# GPIO.net
KiCad netlist of a schematic drawn in Altium Designer
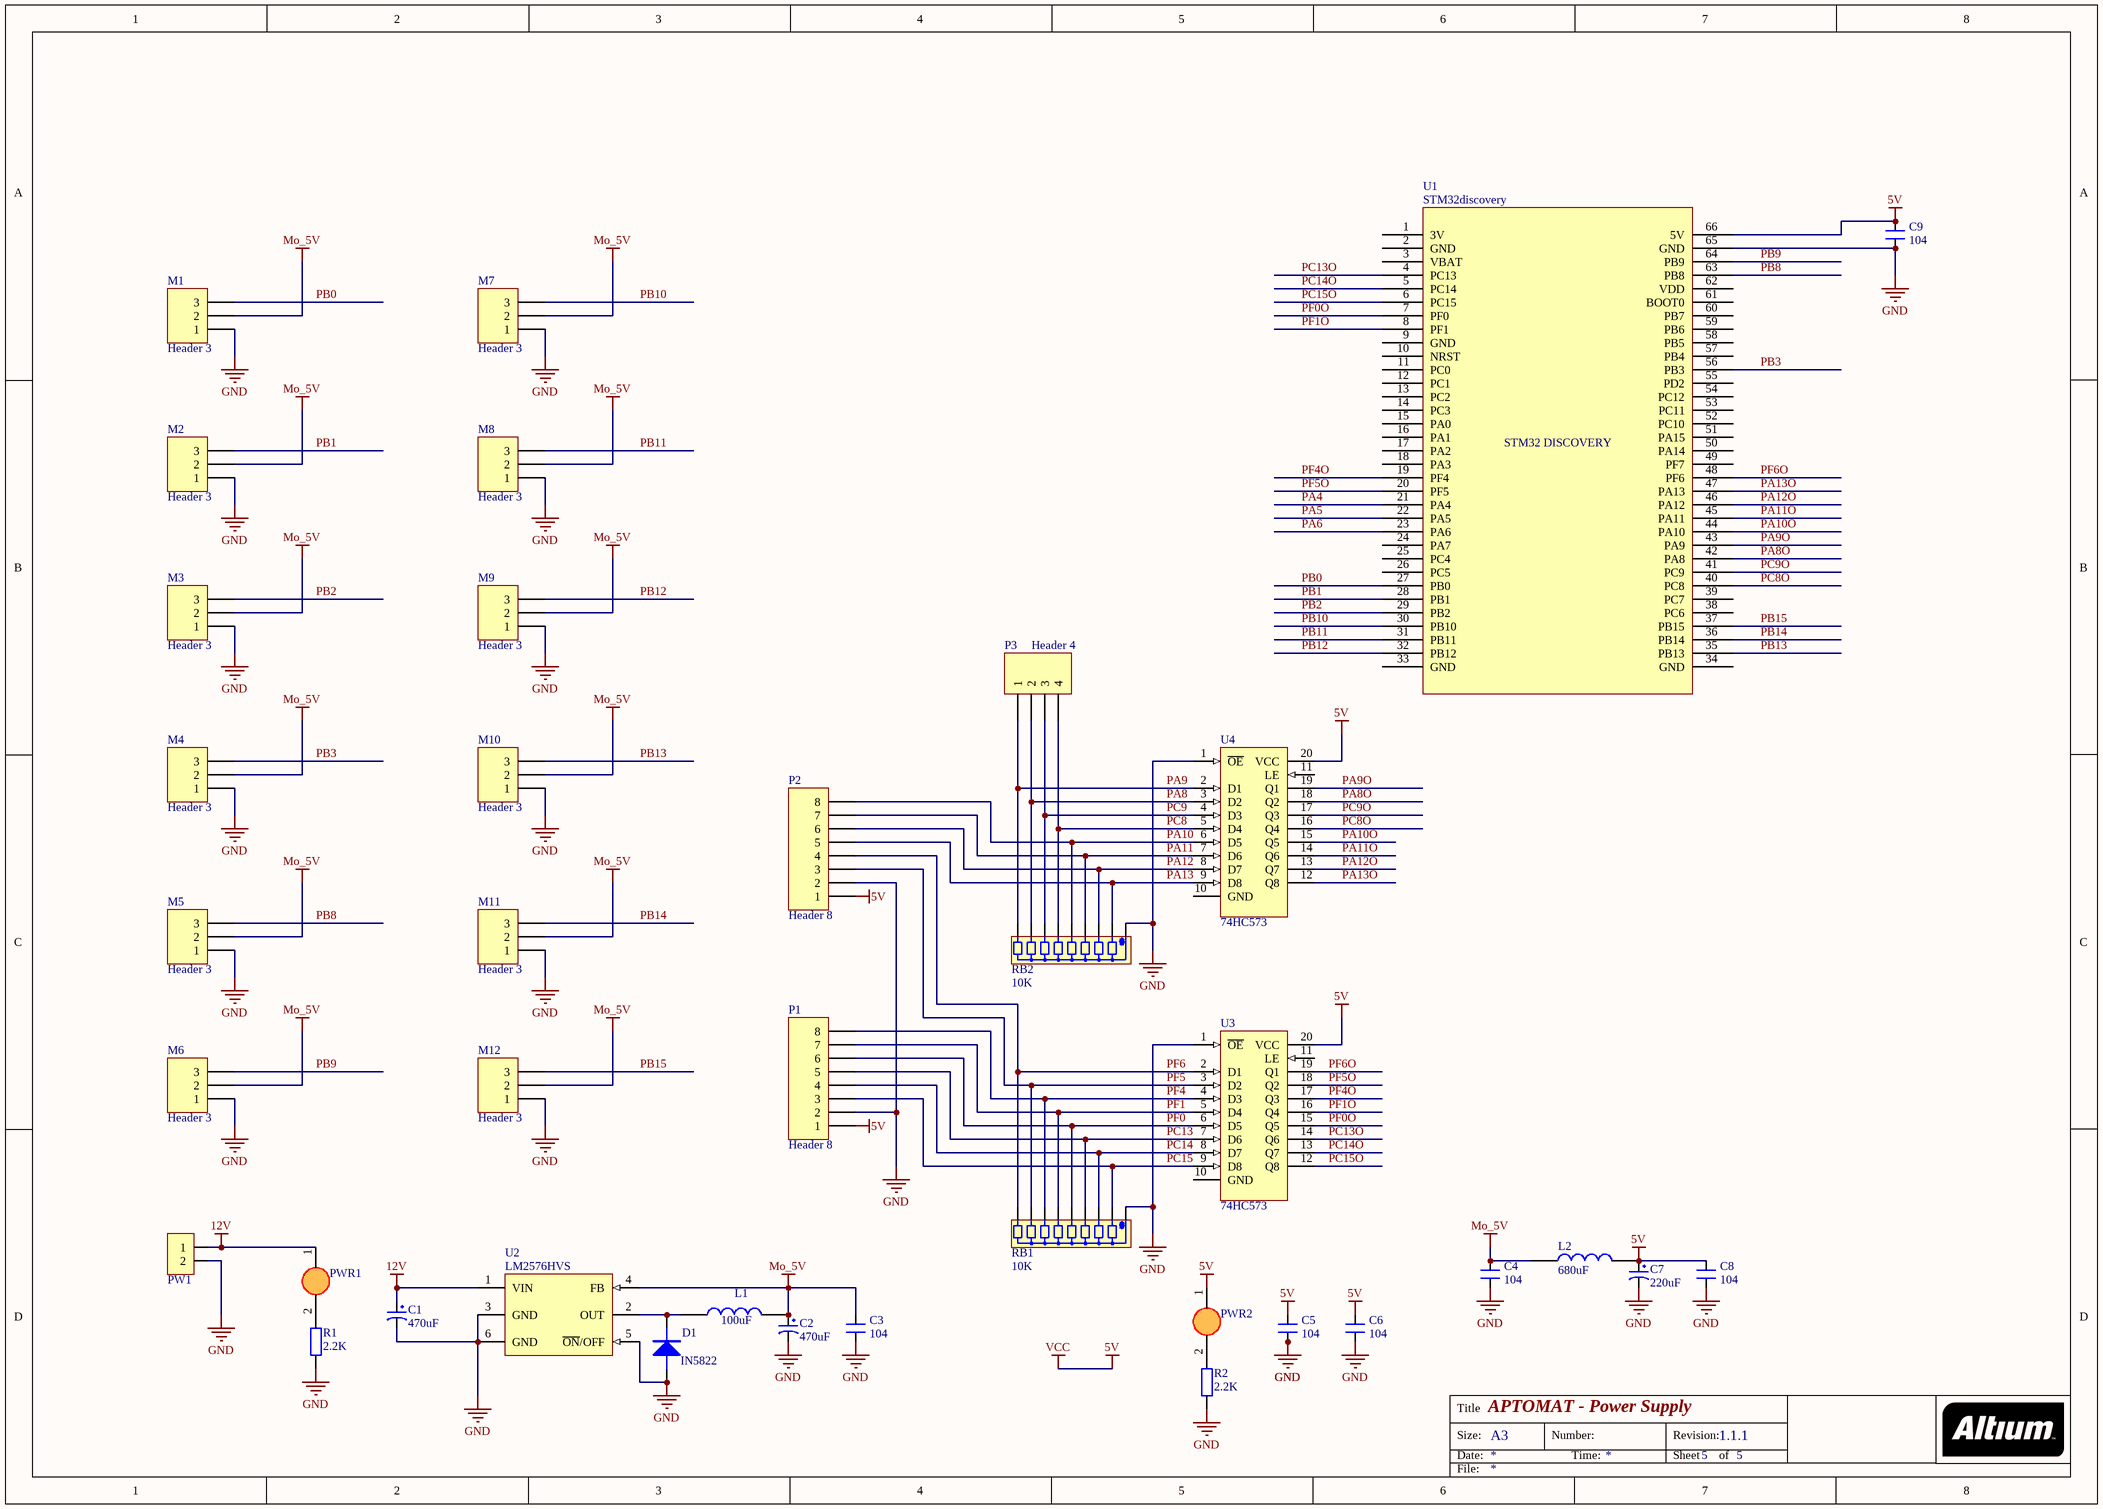
[diagram p0: GPIO.SchDoc]

(export (version "E")
  (design (tool "Eeschema 10.0.6"))
  (components
    (comp (ref "C1")
      (value "470uF")
      (footprint "TU_NHOM_470uF_25V_MH")
      (description "TU_NHOM_470uF_25V_MH")
      (libsource (lib "MH_DA_THU_VIEN_16122016") (part "TU_NHOM_470uF_25V_MH"))
    )
    (comp (ref "C2")
      (value "470uF")
      (footprint "TU_NHOM_470uF_25V_MH")
      (description "TU_NHOM_470uF_25V_MH")
      (libsource (lib "MH_DA_THU_VIEN_16122016") (part "TU_NHOM_470uF_25V_MH"))
    )
    (comp (ref "C3")
      (value "104")
      (footprint "0805_HV")
      (description "Cap SMD")
      (libsource (lib "hatcatbietbay") (part "CM"))
    )
    (comp (ref "C4")
      (value "104")
      (footprint "0805_HV")
      (description "Cap SMD")
      (libsource (lib "hatcatbietbay") (part "CM"))
    )
    (comp (ref "C5")
      (value "104")
      (footprint "0805_HV")
      (description "Cap SMD")
      (libsource (lib "hatcatbietbay") (part "CM"))
    )
    (comp (ref "C6")
      (value "104")
      (footprint "0805_HV")
      (description "Cap SMD")
      (libsource (lib "hatcatbietbay") (part "CM"))
    )
    (comp (ref "C7")
      (value "220uF")
      (footprint "TU_NHOM_2.5_MH")
      (description "TU_NHOM_220uF_25V_MH")
      (libsource (lib "MH_DA_THU_VIEN_16122016") (part "TU_NHOM_220uF_25V_MH"))
    )
    (comp (ref "C8")
      (value "104")
      (footprint "0805_HV")
      (description "Cap SMD")
      (libsource (lib "hatcatbietbay") (part "CM"))
    )
    (comp (ref "C9")
      (value "104")
      (footprint "0805_HV")
      (description "Cap SMD")
      (libsource (lib "hatcatbietbay") (part "CM"))
    )
    (comp (ref "D1")
      (value "IN5822")
      (footprint "SOD123")
      (description "Diode S4 SOD123 ( 1N5819 SOD123)")
      (libsource (lib "MH_DA_THU_VIEN_16122016") (part "Diode S4 SOD123 ( 1N5819 SOD123)_MH"))
    )
    (comp (ref "L1")
      (value "100uF")
      (footprint "IND_2118-V-RC")
      (description "cuon cam")
      (libsource (lib "MH_DA_THU_VIEN_16122016") (part "Inductor Lm2576_MH"))
    )
    (comp (ref "L2")
      (value "680uF")
      (footprint "Inductor 4.5x5")
      (libsource (lib "MH_DA_THU_VIEN_16122016") (part "Inductor 4.5x5_MH"))
    )
    (comp (ref "M1")
      (value "Header 3")
      (footprint "HDR1X3")
      (description "Header, 3-Pin")
      (fields (field (name "PUBLISHER") "Altium Limited"))
      (libsource (lib "Miscellaneous Connectors") (part "Header 3"))
    )
    (comp (ref "M2")
      (value "Header 3")
      (footprint "HDR1X3")
      (description "Header, 3-Pin")
      (fields (field (name "PUBLISHER") "Altium Limited"))
      (libsource (lib "Miscellaneous Connectors") (part "Header 3"))
    )
    (comp (ref "M3")
      (value "Header 3")
      (footprint "HDR1X3")
      (description "Header, 3-Pin")
      (fields (field (name "PUBLISHER") "Altium Limited"))
      (libsource (lib "Miscellaneous Connectors") (part "Header 3"))
    )
    (comp (ref "M4")
      (value "Header 3")
      (footprint "HDR1X3")
      (description "Header, 3-Pin")
      (fields (field (name "PUBLISHER") "Altium Limited"))
      (libsource (lib "Miscellaneous Connectors") (part "Header 3"))
    )
    (comp (ref "M5")
      (value "Header 3")
      (footprint "HDR1X3")
      (description "Header, 3-Pin")
      (fields (field (name "PUBLISHER") "Altium Limited"))
      (libsource (lib "Miscellaneous Connectors") (part "Header 3"))
    )
    (comp (ref "M6")
      (value "Header 3")
      (footprint "HDR1X3")
      (description "Header, 3-Pin")
      (fields (field (name "PUBLISHER") "Altium Limited"))
      (libsource (lib "Miscellaneous Connectors") (part "Header 3"))
    )
    (comp (ref "M7")
      (value "Header 3")
      (footprint "HDR1X3")
      (description "Header, 3-Pin")
      (fields (field (name "PUBLISHER") "Altium Limited"))
      (libsource (lib "Miscellaneous Connectors") (part "Header 3"))
    )
    (comp (ref "M8")
      (value "Header 3")
      (footprint "HDR1X3")
      (description "Header, 3-Pin")
      (fields (field (name "PUBLISHER") "Altium Limited"))
      (libsource (lib "Miscellaneous Connectors") (part "Header 3"))
    )
    (comp (ref "M9")
      (value "Header 3")
      (footprint "HDR1X3")
      (description "Header, 3-Pin")
      (fields (field (name "PUBLISHER") "Altium Limited"))
      (libsource (lib "Miscellaneous Connectors") (part "Header 3"))
    )
    (comp (ref "M10")
      (value "Header 3")
      (footprint "HDR1X3")
      (description "Header, 3-Pin")
      (fields (field (name "PUBLISHER") "Altium Limited"))
      (libsource (lib "Miscellaneous Connectors") (part "Header 3"))
    )
    (comp (ref "M11")
      (value "Header 3")
      (footprint "HDR1X3")
      (description "Header, 3-Pin")
      (fields (field (name "PUBLISHER") "Altium Limited"))
      (libsource (lib "Miscellaneous Connectors") (part "Header 3"))
    )
    (comp (ref "M12")
      (value "Header 3")
      (footprint "HDR1X3")
      (description "Header, 3-Pin")
      (fields (field (name "PUBLISHER") "Altium Limited"))
      (libsource (lib "Miscellaneous Connectors") (part "Header 3"))
    )
    (comp (ref "P1")
      (value "Header 8")
      (footprint "HEADER2M_8P")
      (description "Header, 8-Pin")
      (fields (field (name "PUBLISHER") "Altium Limited"))
      (libsource (lib "Miscellaneous Connectors") (part "Header 8"))
    )
    (comp (ref "P2")
      (value "Header 8")
      (footprint "HEADER2M_8P")
      (description "Header, 8-Pin")
      (fields (field (name "PUBLISHER") "Altium Limited"))
      (libsource (lib "Miscellaneous Connectors") (part "Header 8"))
    )
    (comp (ref "P3")
      (value "Header 4")
      (footprint "HDR1X4")
      (description "Header, 4-Pin")
      (fields (field (name "PUBLISHER") "Altium Limited"))
      (libsource (lib "Miscellaneous Connectors") (part "Header 4"))
    )
    (comp (ref "PW1")
      (value "CON 2 EDG 5.08_MH")
      (footprint "CON 2 EDG 5.08")
      (description "CON 2 EDG 5.08 (xanh cong)")
      (libsource (lib "MH_DA_THU_VIEN_16122016") (part "CON 2 EDG 5.08_MH"))
    )
    (comp (ref "PWR1")
      (value "LED3")
      (footprint "LED_0805")
      (description "LED 3mm")
      (libsource (lib "MH_DA_THU_VIEN_16122016") (part "LED SMD_0805_MH"))
    )
    (comp (ref "PWR2")
      (value "LED3")
      (footprint "LED_0805")
      (description "LED 3mm")
      (libsource (lib "MH_DA_THU_VIEN_16122016") (part "LED SMD_0805_MH"))
    )
    (comp (ref "R1")
      (value "2.2K")
      (footprint "MH_DA_THU_VIEN_16122016:Tro SMD 0805")
      (description "TRO_SMD_0805_MH")
      (libsource (lib "MH_DA_THU_VIEN_16122016") (part "TRO_SMD_0805_MH"))
    )
    (comp (ref "R2")
      (value "2.2K")
      (footprint "MH_DA_THU_VIEN_16122016:Tro SMD 0805")
      (description "TRO_SMD_0805_MH")
      (libsource (lib "MH_DA_THU_VIEN_16122016") (part "TRO_SMD_0805_MH"))
    )
    (comp (ref "RB1")
      (value "TRO_BANG_A09_MH")
      (footprint "TRO_BANG_A09")
      (fields (field (name "ALTIUM_UNNAMED_1") "10K"))
      (libsource (lib "MH_DA_THU_VIEN_16122016") (part "TRO_BANG_A09_MH"))
    )
    (comp (ref "RB2")
      (value "TRO_BANG_A09_MH")
      (footprint "TRO_BANG_A09")
      (fields (field (name "ALTIUM_UNNAMED_1") "10K"))
      (libsource (lib "MH_DA_THU_VIEN_16122016") (part "TRO_BANG_A09_MH"))
    )
    (comp (ref "U1")
      (value "STM32discovery")
      (footprint "STM32discovery_kit")
      (libsource (lib "Schlib1") (part "STM32Discovery_kit"))
    )
    (comp (ref "U2")
      (value "LM2576HVS")
      (footprint "TO263-5")
      (description "LM2576HVS-5.0V BUCK 5V 3A TO263-5 _MH")
      (fields
        (field (name "PARTNUMBER") "LM2576T-5.0")
        (field (name "MANUFACTURER") "National Semiconductor")
        (field (name "PUBLISHER") "Altium Limited")
      )
      (libsource (lib "MH_DA_THU_VIEN_16122016") (part "LM2576HVS-5.0V BUCK 5V 3A TO263-5 _MH"))
    )
    (comp (ref "U3")
      (value "74HC573")
      (footprint "DIP20")
      (description "Octal D-Type Latch with 3-State Output Non-Inverting")
      (fields (field (name "COPYRIGHT BY") "VanDungEvn@Gmail.com"))
      (libsource (lib "MH_DA_THU_VIEN_16122016") (part "74HC573 DIP20 IC Flip-Flop_MH"))
    )
    (comp (ref "U4")
      (value "74HC573")
      (footprint "DIP20")
      (description "Octal D-Type Latch with 3-State Output Non-Inverting")
      (fields (field (name "COPYRIGHT BY") "VanDungEvn@Gmail.com"))
      (libsource (lib "MH_DA_THU_VIEN_16122016") (part "74HC573 DIP20 IC Flip-Flop_MH"))
    )
  )
  (nets
    (net (code "1") (name "/PA4") (class "Default")
      (node (ref "U1") (pin "21") (pinfunction "PA4_21") (pintype "passive"))
    )
    (net (code "2") (name "/PA5") (class "Default")
      (node (ref "U1") (pin "22") (pinfunction "PA5_22") (pintype "passive"))
    )
    (net (code "3") (name "/PA6") (class "Default")
      (node (ref "U1") (pin "23") (pinfunction "PA6_23") (pintype "passive"))
    )
    (net (code "4") (name "/PA8") (class "Default")
      (node (ref "P3") (pin "2") (pinfunction "2_2") (pintype "passive"))
      (node (ref "RB2") (pin "8") (pinfunction "8_8") (pintype "passive"))
      (node (ref "U4") (pin "3") (pinfunction "D2_3") (pintype "input"))
    )
    (net (code "5") (name "/PA8O") (class "Default")
      (node (ref "U1") (pin "42") (pinfunction "PA8_42") (pintype "passive"))
      (node (ref "U4") (pin "18") (pinfunction "Q2_18") (pintype "tri_state"))
    )
    (net (code "6") (name "/PA9") (class "Default")
      (node (ref "P3") (pin "1") (pinfunction "1_1") (pintype "passive"))
      (node (ref "RB2") (pin "9") (pinfunction "9_9") (pintype "passive"))
      (node (ref "U4") (pin "2") (pinfunction "D1_2") (pintype "input"))
    )
    (net (code "7") (name "/PA9O") (class "Default")
      (node (ref "U1") (pin "43") (pinfunction "PA9_43") (pintype "passive"))
      (node (ref "U4") (pin "19") (pinfunction "Q1_19") (pintype "tri_state"))
    )
    (net (code "8") (name "/PA10") (class "Default")
      (node (ref "P2") (pin "8") (pinfunction "8_8") (pintype "passive"))
      (node (ref "RB2") (pin "5") (pinfunction "5_5") (pintype "passive"))
      (node (ref "U4") (pin "6") (pinfunction "D5_6") (pintype "input"))
    )
    (net (code "9") (name "/PA10O") (class "Default")
      (node (ref "U1") (pin "44") (pinfunction "PA10_44") (pintype "passive"))
      (node (ref "U4") (pin "15") (pinfunction "Q5_15") (pintype "tri_state"))
    )
    (net (code "10") (name "/PA11") (class "Default")
      (node (ref "P2") (pin "7") (pinfunction "7_7") (pintype "passive"))
      (node (ref "RB2") (pin "4") (pinfunction "4_4") (pintype "passive"))
      (node (ref "U4") (pin "7") (pinfunction "D6_7") (pintype "input"))
    )
    (net (code "11") (name "/PA11O") (class "Default")
      (node (ref "U1") (pin "45") (pinfunction "PA11_45") (pintype "passive"))
      (node (ref "U4") (pin "14") (pinfunction "Q6_14") (pintype "tri_state"))
    )
    (net (code "12") (name "/PA12") (class "Default")
      (node (ref "P2") (pin "6") (pinfunction "6_6") (pintype "passive"))
      (node (ref "RB2") (pin "3") (pinfunction "3_3") (pintype "passive"))
      (node (ref "U4") (pin "8") (pinfunction "D7_8") (pintype "input"))
    )
    (net (code "13") (name "/PA12O") (class "Default")
      (node (ref "U1") (pin "46") (pinfunction "PA12_46") (pintype "passive"))
      (node (ref "U4") (pin "13") (pinfunction "Q7_13") (pintype "tri_state"))
    )
    (net (code "14") (name "/PA13") (class "Default")
      (node (ref "P2") (pin "5") (pinfunction "5_5") (pintype "passive"))
      (node (ref "RB2") (pin "2") (pinfunction "2_2") (pintype "passive"))
      (node (ref "U4") (pin "9") (pinfunction "D8_9") (pintype "input"))
    )
    (net (code "15") (name "/PA13O") (class "Default")
      (node (ref "U1") (pin "47") (pinfunction "PA13_47") (pintype "passive"))
      (node (ref "U4") (pin "12") (pinfunction "Q8_12") (pintype "tri_state"))
    )
    (net (code "16") (name "/PB0") (class "Default")
      (node (ref "M1") (pin "3") (pinfunction "3_3") (pintype "passive"))
      (node (ref "U1") (pin "27") (pinfunction "PB0_27") (pintype "passive"))
    )
    (net (code "17") (name "/PB1") (class "Default")
      (node (ref "M2") (pin "3") (pinfunction "3_3") (pintype "passive"))
      (node (ref "U1") (pin "28") (pinfunction "PB1_28") (pintype "passive"))
    )
    (net (code "18") (name "/PB2") (class "Default")
      (node (ref "M3") (pin "3") (pinfunction "3_3") (pintype "passive"))
      (node (ref "U1") (pin "29") (pinfunction "PB2_29") (pintype "passive"))
    )
    (net (code "19") (name "/PB3") (class "Default")
      (node (ref "M4") (pin "3") (pinfunction "3_3") (pintype "passive"))
      (node (ref "U1") (pin "56") (pinfunction "PB3_56") (pintype "passive"))
    )
    (net (code "20") (name "/PB8") (class "Default")
      (node (ref "M5") (pin "3") (pinfunction "3_3") (pintype "passive"))
      (node (ref "U1") (pin "63") (pinfunction "PB8_63") (pintype "passive"))
    )
    (net (code "21") (name "/PB9") (class "Default")
      (node (ref "M6") (pin "3") (pinfunction "3_3") (pintype "passive"))
      (node (ref "U1") (pin "64") (pinfunction "PB9_64") (pintype "passive"))
    )
    (net (code "22") (name "/PB10") (class "Default")
      (node (ref "M7") (pin "3") (pinfunction "3_3") (pintype "passive"))
      (node (ref "U1") (pin "30") (pinfunction "PB10_30") (pintype "passive"))
    )
    (net (code "23") (name "/PB11") (class "Default")
      (node (ref "M8") (pin "3") (pinfunction "3_3") (pintype "passive"))
      (node (ref "U1") (pin "31") (pinfunction "PB11_31") (pintype "passive"))
    )
    (net (code "24") (name "/PB12") (class "Default")
      (node (ref "M9") (pin "3") (pinfunction "3_3") (pintype "passive"))
      (node (ref "U1") (pin "32") (pinfunction "PB12_32") (pintype "passive"))
    )
    (net (code "25") (name "/PB13") (class "Default")
      (node (ref "M10") (pin "3") (pinfunction "3_3") (pintype "passive"))
      (node (ref "U1") (pin "35") (pinfunction "PB13_35") (pintype "passive"))
    )
    (net (code "26") (name "/PB14") (class "Default")
      (node (ref "M11") (pin "3") (pinfunction "3_3") (pintype "passive"))
      (node (ref "U1") (pin "36") (pinfunction "PB14_36") (pintype "passive"))
    )
    (net (code "27") (name "/PB15") (class "Default")
      (node (ref "M12") (pin "3") (pinfunction "3_3") (pintype "passive"))
      (node (ref "U1") (pin "37") (pinfunction "PB15_37") (pintype "passive"))
    )
    (net (code "28") (name "/PC8") (class "Default")
      (node (ref "P3") (pin "4") (pinfunction "4_4") (pintype "passive"))
      (node (ref "RB2") (pin "6") (pinfunction "6_6") (pintype "passive"))
      (node (ref "U4") (pin "5") (pinfunction "D4_5") (pintype "input"))
    )
    (net (code "29") (name "/PC8O") (class "Default")
      (node (ref "U1") (pin "40") (pinfunction "PC8_40") (pintype "passive"))
      (node (ref "U4") (pin "16") (pinfunction "Q4_16") (pintype "tri_state"))
    )
    (net (code "30") (name "/PC9") (class "Default")
      (node (ref "P3") (pin "3") (pinfunction "3_3") (pintype "passive"))
      (node (ref "RB2") (pin "7") (pinfunction "7_7") (pintype "passive"))
      (node (ref "U4") (pin "4") (pinfunction "D3_4") (pintype "input"))
    )
    (net (code "31") (name "/PC9O") (class "Default")
      (node (ref "U1") (pin "41") (pinfunction "PC9_41") (pintype "passive"))
      (node (ref "U4") (pin "17") (pinfunction "Q3_17") (pintype "tri_state"))
    )
    (net (code "32") (name "/PC13") (class "Default")
      (node (ref "P1") (pin "5") (pinfunction "5_5") (pintype "passive"))
      (node (ref "RB1") (pin "4") (pinfunction "4_4") (pintype "passive"))
      (node (ref "U3") (pin "7") (pinfunction "D6_7") (pintype "input"))
    )
    (net (code "33") (name "/PC13O") (class "Default")
      (node (ref "U1") (pin "4") (pinfunction "PC13_4") (pintype "passive"))
      (node (ref "U3") (pin "14") (pinfunction "Q6_14") (pintype "tri_state"))
    )
    (net (code "34") (name "/PC14") (class "Default")
      (node (ref "P1") (pin "4") (pinfunction "4_4") (pintype "passive"))
      (node (ref "RB1") (pin "3") (pinfunction "3_3") (pintype "passive"))
      (node (ref "U3") (pin "8") (pinfunction "D7_8") (pintype "input"))
    )
    (net (code "35") (name "/PC14O") (class "Default")
      (node (ref "U1") (pin "5") (pinfunction "PC14_5") (pintype "passive"))
      (node (ref "U3") (pin "13") (pinfunction "Q7_13") (pintype "tri_state"))
    )
    (net (code "36") (name "/PC15") (class "Default")
      (node (ref "P1") (pin "3") (pinfunction "3_3") (pintype "passive"))
      (node (ref "RB1") (pin "2") (pinfunction "2_2") (pintype "passive"))
      (node (ref "U3") (pin "9") (pinfunction "D8_9") (pintype "input"))
    )
    (net (code "37") (name "/PC15O") (class "Default")
      (node (ref "U1") (pin "6") (pinfunction "PC15_6") (pintype "passive"))
      (node (ref "U3") (pin "12") (pinfunction "Q8_12") (pintype "tri_state"))
    )
    (net (code "38") (name "/PF0") (class "Default")
      (node (ref "P1") (pin "6") (pinfunction "6_6") (pintype "passive"))
      (node (ref "RB1") (pin "5") (pinfunction "5_5") (pintype "passive"))
      (node (ref "U3") (pin "6") (pinfunction "D5_6") (pintype "input"))
    )
    (net (code "39") (name "/PF0O") (class "Default")
      (node (ref "U1") (pin "7") (pinfunction "PF0_7") (pintype "passive"))
      (node (ref "U3") (pin "15") (pinfunction "Q5_15") (pintype "tri_state"))
    )
    (net (code "40") (name "/PF1") (class "Default")
      (node (ref "P1") (pin "7") (pinfunction "7_7") (pintype "passive"))
      (node (ref "RB1") (pin "6") (pinfunction "6_6") (pintype "passive"))
      (node (ref "U3") (pin "5") (pinfunction "D4_5") (pintype "input"))
    )
    (net (code "41") (name "/PF1O") (class "Default")
      (node (ref "U1") (pin "8") (pinfunction "PF1_8") (pintype "passive"))
      (node (ref "U3") (pin "16") (pinfunction "Q4_16") (pintype "tri_state"))
    )
    (net (code "42") (name "/PF4") (class "Default")
      (node (ref "P1") (pin "8") (pinfunction "8_8") (pintype "passive"))
      (node (ref "RB1") (pin "7") (pinfunction "7_7") (pintype "passive"))
      (node (ref "U3") (pin "4") (pinfunction "D3_4") (pintype "input"))
    )
    (net (code "43") (name "/PF4O") (class "Default")
      (node (ref "U1") (pin "19") (pinfunction "PF4_19") (pintype "passive"))
      (node (ref "U3") (pin "17") (pinfunction "Q3_17") (pintype "tri_state"))
    )
    (net (code "44") (name "/PF5") (class "Default")
      (node (ref "P2") (pin "3") (pinfunction "3_3") (pintype "passive"))
      (node (ref "RB1") (pin "8") (pinfunction "8_8") (pintype "passive"))
      (node (ref "U3") (pin "3") (pinfunction "D2_3") (pintype "input"))
    )
    (net (code "45") (name "/PF5O") (class "Default")
      (node (ref "U1") (pin "20") (pinfunction "PF5_20") (pintype "passive"))
      (node (ref "U3") (pin "18") (pinfunction "Q2_18") (pintype "tri_state"))
    )
    (net (code "46") (name "/PF6") (class "Default")
      (node (ref "P2") (pin "4") (pinfunction "4_4") (pintype "passive"))
      (node (ref "RB1") (pin "9") (pinfunction "9_9") (pintype "passive"))
      (node (ref "U3") (pin "2") (pinfunction "D1_2") (pintype "input"))
    )
    (net (code "47") (name "/PF6O") (class "Default")
      (node (ref "U1") (pin "48") (pinfunction "PF6_48") (pintype "passive"))
      (node (ref "U3") (pin "19") (pinfunction "Q1_19") (pintype "tri_state"))
    )
    (net (code "48") (name "5V") (class "Default")
      (node (ref "C5") (pin "2") (pinfunction "2_2") (pintype "passive"))
      (node (ref "C6") (pin "2") (pinfunction "2_2") (pintype "passive"))
      (node (ref "C7") (pin "1") (pinfunction "1_1") (pintype "passive"))
      (node (ref "C8") (pin "2") (pinfunction "2_2") (pintype "passive"))
      (node (ref "C9") (pin "2") (pinfunction "2_2") (pintype "passive"))
      (node (ref "L2") (pin "2") (pinfunction "2_2") (pintype "passive"))
      (node (ref "P1") (pin "1") (pinfunction "1_1") (pintype "passive"))
      (node (ref "P2") (pin "1") (pinfunction "1_1") (pintype "passive"))
      (node (ref "PWR2") (pin "1") (pinfunction "A_1") (pintype "passive"))
      (node (ref "U1") (pin "66") (pinfunction "5V_66") (pintype "passive"))
      (node (ref "U3") (pin "20") (pinfunction "VCC_20") (pintype "tri_state"))
      (node (ref "U4") (pin "20") (pinfunction "VCC_20") (pintype "tri_state"))
    )
    (net (code "49") (name "12V") (class "Default")
      (node (ref "C1") (pin "1") (pinfunction "1_1") (pintype "passive"))
      (node (ref "PW1") (pin "1") (pinfunction "1_1") (pintype "passive"))
      (node (ref "PWR1") (pin "1") (pinfunction "A_1") (pintype "passive"))
      (node (ref "U2") (pin "1") (pinfunction "VIN_1") (pintype "power_in"))
    )
    (net (code "50") (name "GND") (class "Default")
      (node (ref "C1") (pin "2") (pinfunction "2_2") (pintype "passive"))
      (node (ref "C2") (pin "2") (pinfunction "2_2") (pintype "passive"))
      (node (ref "C3") (pin "1") (pinfunction "1_1") (pintype "passive"))
      (node (ref "C4") (pin "1") (pinfunction "1_1") (pintype "passive"))
      (node (ref "C5") (pin "1") (pinfunction "1_1") (pintype "passive"))
      (node (ref "C6") (pin "1") (pinfunction "1_1") (pintype "passive"))
      (node (ref "C7") (pin "2") (pinfunction "2_2") (pintype "passive"))
      (node (ref "C8") (pin "1") (pinfunction "1_1") (pintype "passive"))
      (node (ref "C9") (pin "1") (pinfunction "1_1") (pintype "passive"))
      (node (ref "D1") (pin "1") (pinfunction "1_1") (pintype "passive"))
      (node (ref "M1") (pin "1") (pinfunction "1_1") (pintype "passive"))
      (node (ref "M10") (pin "1") (pinfunction "1_1") (pintype "passive"))
      (node (ref "M11") (pin "1") (pinfunction "1_1") (pintype "passive"))
      (node (ref "M12") (pin "1") (pinfunction "1_1") (pintype "passive"))
      (node (ref "M2") (pin "1") (pinfunction "1_1") (pintype "passive"))
      (node (ref "M3") (pin "1") (pinfunction "1_1") (pintype "passive"))
      (node (ref "M4") (pin "1") (pinfunction "1_1") (pintype "passive"))
      (node (ref "M5") (pin "1") (pinfunction "1_1") (pintype "passive"))
      (node (ref "M6") (pin "1") (pinfunction "1_1") (pintype "passive"))
      (node (ref "M7") (pin "1") (pinfunction "1_1") (pintype "passive"))
      (node (ref "M8") (pin "1") (pinfunction "1_1") (pintype "passive"))
      (node (ref "M9") (pin "1") (pinfunction "1_1") (pintype "passive"))
      (node (ref "P1") (pin "2") (pinfunction "2_2") (pintype "passive"))
      (node (ref "P2") (pin "2") (pinfunction "2_2") (pintype "passive"))
      (node (ref "PW1") (pin "2") (pinfunction "2_2") (pintype "passive"))
      (node (ref "R1") (pin "1") (pinfunction "1_1") (pintype "passive"))
      (node (ref "R2") (pin "1") (pinfunction "1_1") (pintype "passive"))
      (node (ref "RB1") (pin "1") (pinfunction "1_1") (pintype "passive"))
      (node (ref "RB2") (pin "1") (pinfunction "1_1") (pintype "passive"))
      (node (ref "U1") (pin "65") (pinfunction "GND_65") (pintype "passive"))
      (node (ref "U2") (pin "3") (pinfunction "GND_3") (pintype "power_in"))
      (node (ref "U2") (pin "5") (pinfunction "~{ON}/OFF_5") (pintype "input"))
      (node (ref "U2") (pin "6") (pinfunction "GND_6") (pintype "passive"))
      (node (ref "U3") (pin "1") (pinfunction "~{OE}_1") (pintype "input"))
      (node (ref "U4") (pin "1") (pinfunction "~{OE}_1") (pintype "input"))
    )
    (net (code "51") (name "Mo_5V") (class "Default")
      (node (ref "C2") (pin "1") (pinfunction "1_1") (pintype "passive"))
      (node (ref "C3") (pin "2") (pinfunction "2_2") (pintype "passive"))
      (node (ref "C4") (pin "2") (pinfunction "2_2") (pintype "passive"))
      (node (ref "L1") (pin "2") (pinfunction "2_2") (pintype "passive"))
      (node (ref "L2") (pin "1") (pinfunction "1_1") (pintype "passive"))
      (node (ref "M1") (pin "2") (pinfunction "2_2") (pintype "passive"))
      (node (ref "M10") (pin "2") (pinfunction "2_2") (pintype "passive"))
      (node (ref "M11") (pin "2") (pinfunction "2_2") (pintype "passive"))
      (node (ref "M12") (pin "2") (pinfunction "2_2") (pintype "passive"))
      (node (ref "M2") (pin "2") (pinfunction "2_2") (pintype "passive"))
      (node (ref "M3") (pin "2") (pinfunction "2_2") (pintype "passive"))
      (node (ref "M4") (pin "2") (pinfunction "2_2") (pintype "passive"))
      (node (ref "M5") (pin "2") (pinfunction "2_2") (pintype "passive"))
      (node (ref "M6") (pin "2") (pinfunction "2_2") (pintype "passive"))
      (node (ref "M7") (pin "2") (pinfunction "2_2") (pintype "passive"))
      (node (ref "M8") (pin "2") (pinfunction "2_2") (pintype "passive"))
      (node (ref "M9") (pin "2") (pinfunction "2_2") (pintype "passive"))
      (node (ref "U2") (pin "4") (pinfunction "FB_4") (pintype "input"))
    )
    (net (code "52") (name "Net-(PWR1-K)") (class "Default")
      (node (ref "PWR1") (pin "2") (pinfunction "K_2") (pintype "passive"))
      (node (ref "R1") (pin "2") (pinfunction "2_2") (pintype "passive"))
    )
    (net (code "53") (name "Net-(PWR2-K)") (class "Default")
      (node (ref "PWR2") (pin "2") (pinfunction "K_2") (pintype "passive"))
      (node (ref "R2") (pin "2") (pinfunction "2_2") (pintype "passive"))
    )
    (net (code "54") (name "Net-(U2-OUT)") (class "Default")
      (node (ref "D1") (pin "2") (pinfunction "2_2") (pintype "passive"))
      (node (ref "L1") (pin "1") (pinfunction "1_1") (pintype "passive"))
      (node (ref "U2") (pin "2") (pinfunction "OUT_2") (pintype "power_in"))
    )
    (net (code "55") (name "unconnected-(U1-3V-Pad1)") (class "Default")
      (node (ref "U1") (pin "1") (pinfunction "3V_1") (pintype "passive"))
    )
    (net (code "56") (name "unconnected-(U1-BOOT0-Pad61)") (class "Default")
      (node (ref "U1") (pin "61") (pinfunction "BOOT0_61") (pintype "passive"))
    )
    (net (code "57") (name "unconnected-(U1-GND-Pad2)") (class "Default")
      (node (ref "U1") (pin "2") (pinfunction "GND_2") (pintype "passive"))
    )
    (net (code "58") (name "unconnected-(U1-GND-Pad9)") (class "Default")
      (node (ref "U1") (pin "9") (pinfunction "GND_9") (pintype "passive"))
    )
    (net (code "59") (name "unconnected-(U1-GND-Pad33)") (class "Default")
      (node (ref "U1") (pin "33") (pinfunction "GND_33") (pintype "passive"))
    )
    (net (code "60") (name "unconnected-(U1-GND-Pad34)") (class "Default")
      (node (ref "U1") (pin "34") (pinfunction "GND_34") (pintype "passive"))
    )
    (net (code "61") (name "unconnected-(U1-NRST-Pad10)") (class "Default")
      (node (ref "U1") (pin "10") (pinfunction "NRST_10") (pintype "passive"))
    )
    (net (code "62") (name "unconnected-(U1-PA0-Pad15)") (class "Default")
      (node (ref "U1") (pin "15") (pinfunction "PA0_15") (pintype "passive"))
    )
    (net (code "63") (name "unconnected-(U1-PA1-Pad16)") (class "Default")
      (node (ref "U1") (pin "16") (pinfunction "PA1_16") (pintype "passive"))
    )
    (net (code "64") (name "unconnected-(U1-PA2-Pad17)") (class "Default")
      (node (ref "U1") (pin "17") (pinfunction "PA2_17") (pintype "passive"))
    )
    (net (code "65") (name "unconnected-(U1-PA3-Pad18)") (class "Default")
      (node (ref "U1") (pin "18") (pinfunction "PA3_18") (pintype "passive"))
    )
    (net (code "66") (name "unconnected-(U1-PA7-Pad24)") (class "Default")
      (node (ref "U1") (pin "24") (pinfunction "PA7_24") (pintype "passive"))
    )
    (net (code "67") (name "unconnected-(U1-PA14-Pad50)") (class "Default")
      (node (ref "U1") (pin "50") (pinfunction "PA14_50") (pintype "passive"))
    )
    (net (code "68") (name "unconnected-(U1-PA15-Pad51)") (class "Default")
      (node (ref "U1") (pin "51") (pinfunction "PA15_51") (pintype "passive"))
    )
    (net (code "69") (name "unconnected-(U1-PB4-Pad57)") (class "Default")
      (node (ref "U1") (pin "57") (pinfunction "PB4_57") (pintype "passive"))
    )
    (net (code "70") (name "unconnected-(U1-PB5-Pad58)") (class "Default")
      (node (ref "U1") (pin "58") (pinfunction "PB5_58") (pintype "passive"))
    )
    (net (code "71") (name "unconnected-(U1-PB6-Pad59)") (class "Default")
      (node (ref "U1") (pin "59") (pinfunction "PB6_59") (pintype "passive"))
    )
    (net (code "72") (name "unconnected-(U1-PB7-Pad60)") (class "Default")
      (node (ref "U1") (pin "60") (pinfunction "PB7_60") (pintype "passive"))
    )
    (net (code "73") (name "unconnected-(U1-PC0-Pad11)") (class "Default")
      (node (ref "U1") (pin "11") (pinfunction "PC0_11") (pintype "passive"))
    )
    (net (code "74") (name "unconnected-(U1-PC1-Pad12)") (class "Default")
      (node (ref "U1") (pin "12") (pinfunction "PC1_12") (pintype "passive"))
    )
    (net (code "75") (name "unconnected-(U1-PC2-Pad13)") (class "Default")
      (node (ref "U1") (pin "13") (pinfunction "PC2_13") (pintype "passive"))
    )
    (net (code "76") (name "unconnected-(U1-PC3-Pad14)") (class "Default")
      (node (ref "U1") (pin "14") (pinfunction "PC3_14") (pintype "passive"))
    )
    (net (code "77") (name "unconnected-(U1-PC4-Pad25)") (class "Default")
      (node (ref "U1") (pin "25") (pinfunction "PC4_25") (pintype "passive"))
    )
    (net (code "78") (name "unconnected-(U1-PC5-Pad26)") (class "Default")
      (node (ref "U1") (pin "26") (pinfunction "PC5_26") (pintype "passive"))
    )
    (net (code "79") (name "unconnected-(U1-PC6-Pad38)") (class "Default")
      (node (ref "U1") (pin "38") (pinfunction "PC6_38") (pintype "passive"))
    )
    (net (code "80") (name "unconnected-(U1-PC7-Pad39)") (class "Default")
      (node (ref "U1") (pin "39") (pinfunction "PC7_39") (pintype "passive"))
    )
    (net (code "81") (name "unconnected-(U1-PC10-Pad52)") (class "Default")
      (node (ref "U1") (pin "52") (pinfunction "PC10_52") (pintype "passive"))
    )
    (net (code "82") (name "unconnected-(U1-PC11-Pad53)") (class "Default")
      (node (ref "U1") (pin "53") (pinfunction "PC11_53") (pintype "passive"))
    )
    (net (code "83") (name "unconnected-(U1-PC12-Pad54)") (class "Default")
      (node (ref "U1") (pin "54") (pinfunction "PC12_54") (pintype "passive"))
    )
    (net (code "84") (name "unconnected-(U1-PD2-Pad55)") (class "Default")
      (node (ref "U1") (pin "55") (pinfunction "PD2_55") (pintype "passive"))
    )
    (net (code "85") (name "unconnected-(U1-PF7-Pad49)") (class "Default")
      (node (ref "U1") (pin "49") (pinfunction "PF7_49") (pintype "passive"))
    )
    (net (code "86") (name "unconnected-(U1-VBAT-Pad3)") (class "Default")
      (node (ref "U1") (pin "3") (pinfunction "VBAT_3") (pintype "passive"))
    )
    (net (code "87") (name "unconnected-(U1-VDD-Pad62)") (class "Default")
      (node (ref "U1") (pin "62") (pinfunction "VDD_62") (pintype "passive"))
    )
    (net (code "88") (name "unconnected-(U3-GND-Pad10)") (class "Default")
      (node (ref "U3") (pin "10") (pinfunction "GND_10") (pintype "tri_state"))
    )
    (net (code "89") (name "unconnected-(U3-LE-Pad11)") (class "Default")
      (node (ref "U3") (pin "11") (pinfunction "LE_11") (pintype "input"))
    )
    (net (code "90") (name "unconnected-(U4-GND-Pad10)") (class "Default")
      (node (ref "U4") (pin "10") (pinfunction "GND_10") (pintype "tri_state"))
    )
    (net (code "91") (name "unconnected-(U4-LE-Pad11)") (class "Default")
      (node (ref "U4") (pin "11") (pinfunction "LE_11") (pintype "input"))
    )
  )
)
